# SCH_Minisumo-camara_2026-01-12.net
KiCad netlist of a schematic drawn in EasyEDA
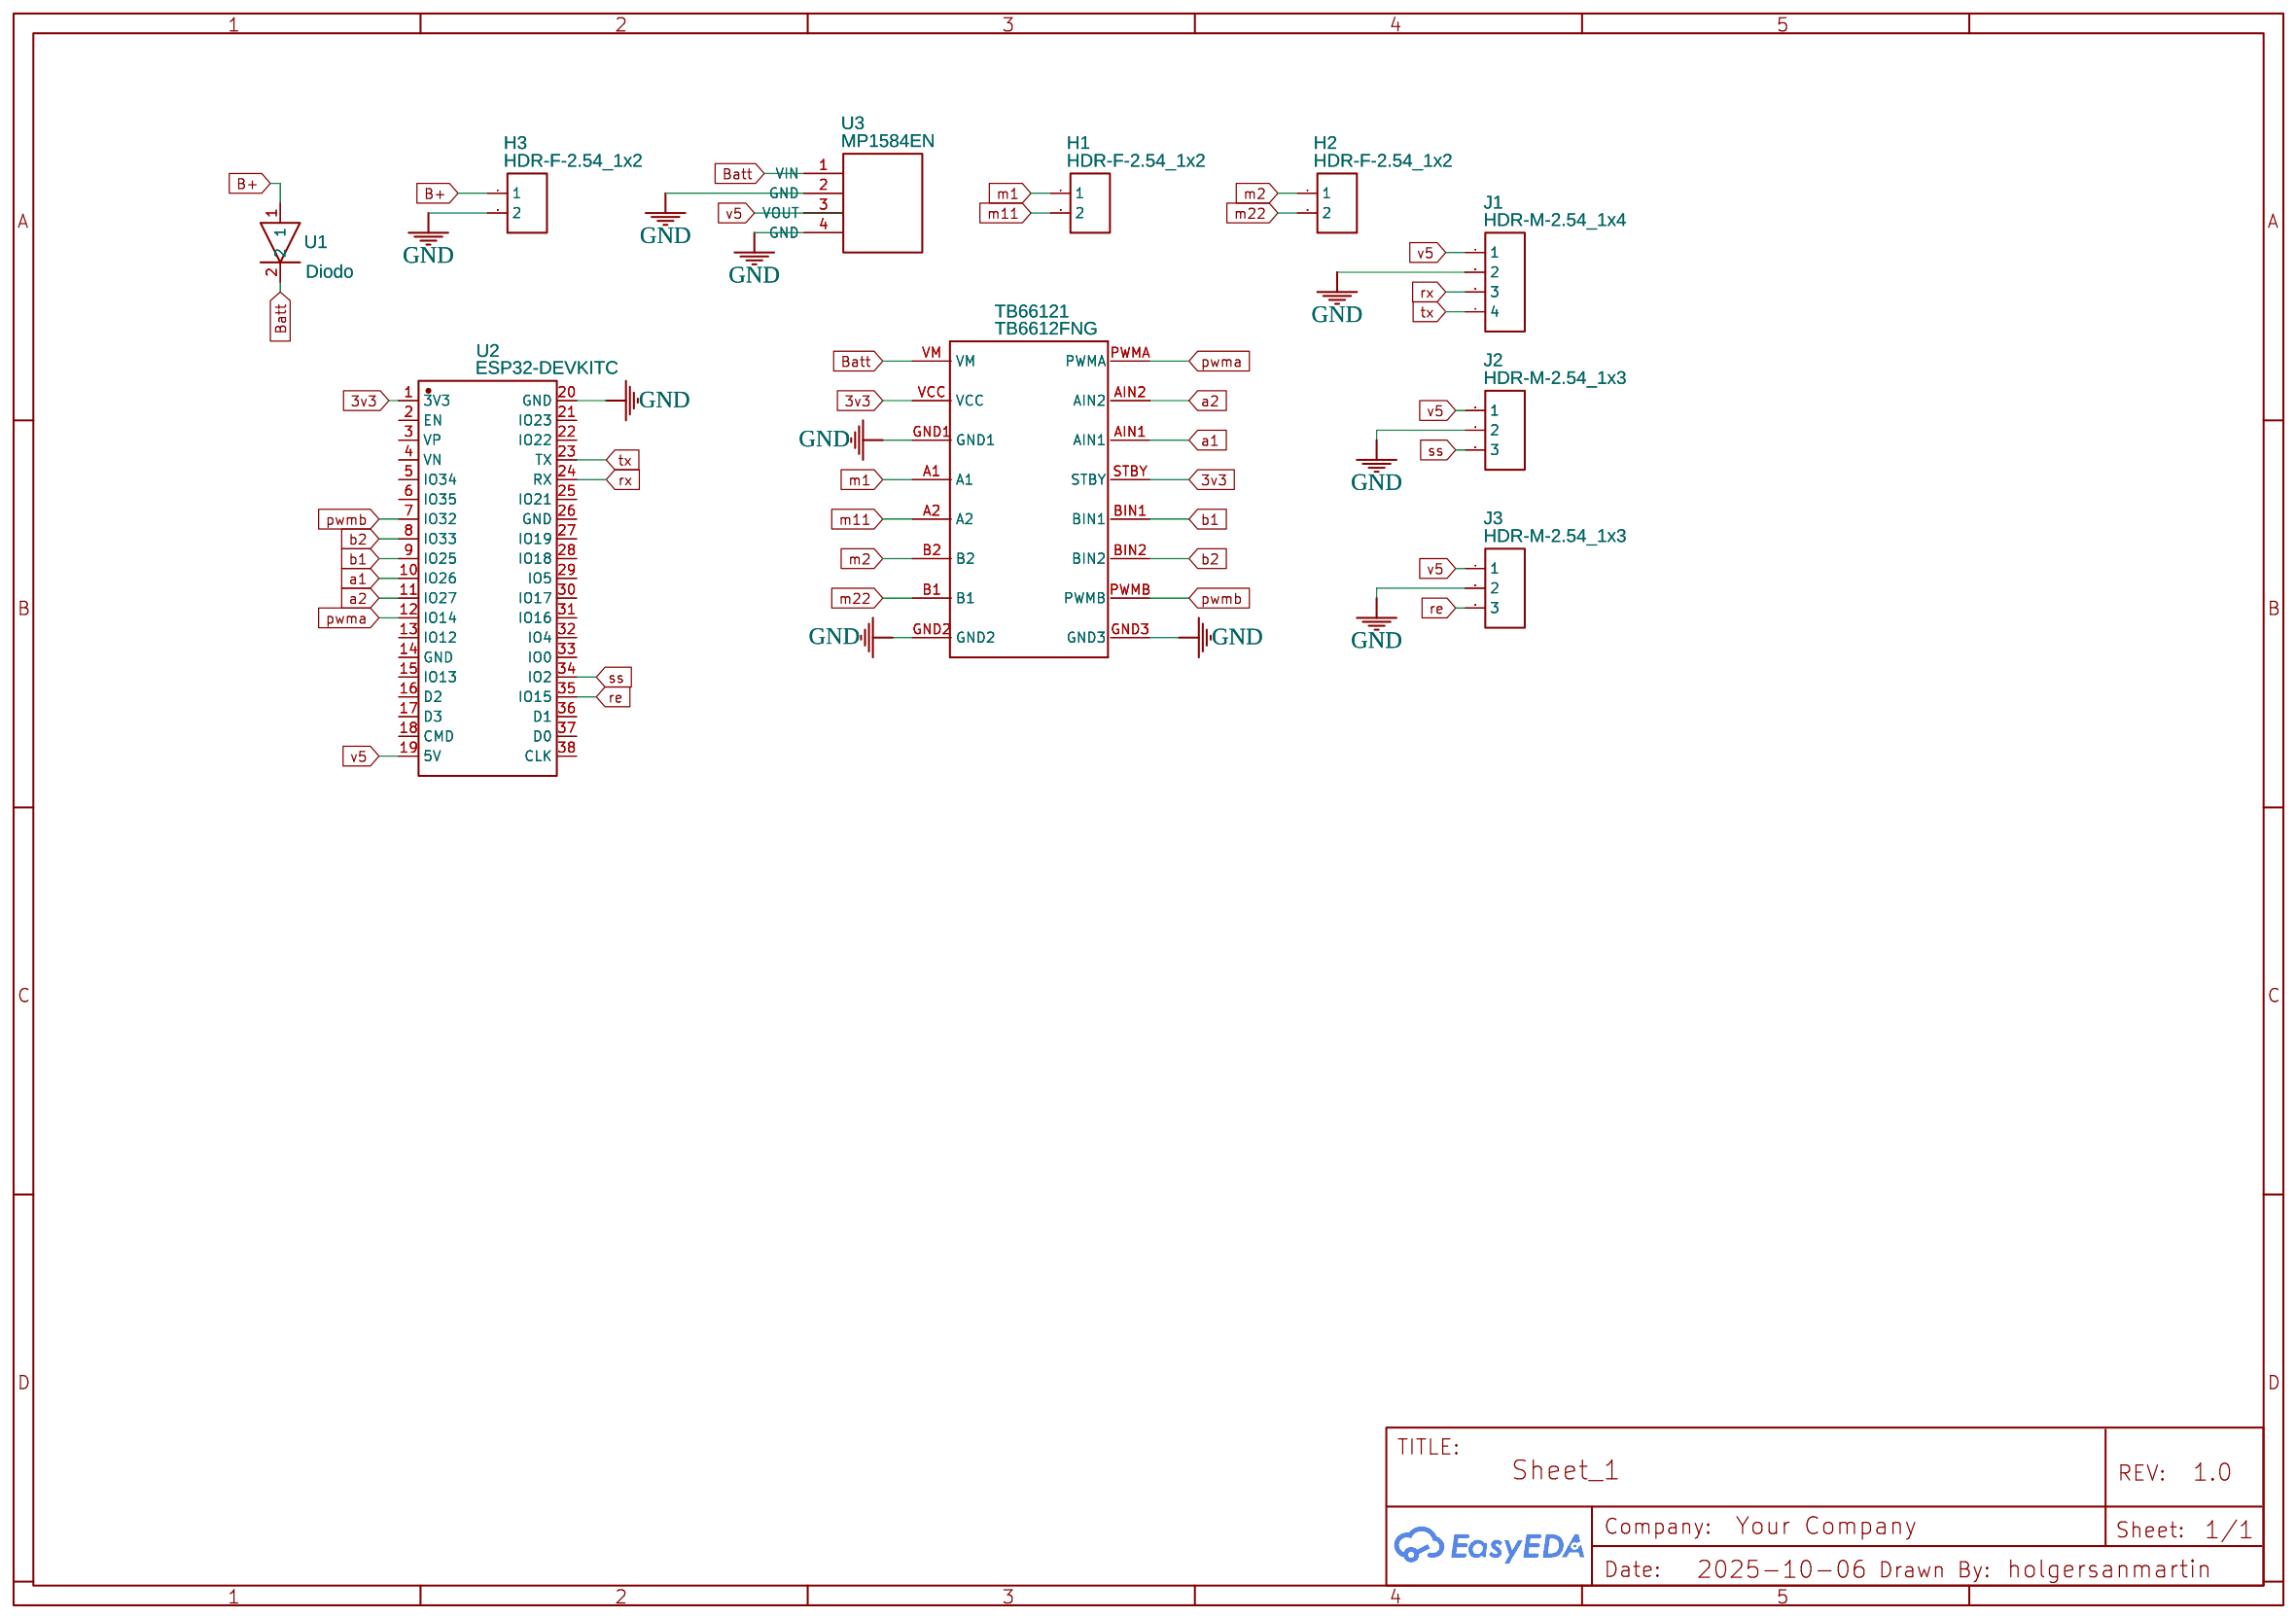
[diagram p0: schematic sheet]

(export (version "E")
  (design (tool "Eeschema 10.0.6"))
  (components
    (comp (ref "H1") (value "HDR-F-2.54_1x2") (libsource (lib "") (part "HDR-F-2.54_1x2")))
    (comp (ref "H2") (value "HDR-F-2.54_1x2") (libsource (lib "") (part "HDR-F-2.54_1x2")))
    (comp (ref "H3") (value "HDR-F-2.54_1x2") (libsource (lib "") (part "HDR-F-2.54_1x2")))
    (comp (ref "J1") (value "HDR-M-2.54_1x4") (libsource (lib "") (part "HDR-M-2.54_1x4")))
    (comp (ref "J2") (value "HDR-M-2.54_1x3") (libsource (lib "") (part "HDR-M-2.54_1x3")))
    (comp (ref "J3") (value "HDR-M-2.54_1x3") (libsource (lib "") (part "HDR-M-2.54_1x3")))
    (comp (ref "TB66121") (value "TB6612FNG") (libsource (lib "") (part "TB6612FNG")))
    (comp (ref "U1") (value "Diodo") (libsource (lib "") (part "Diodo")))
    (comp (ref "U2")
      (value "ESP32-DEVKITC")
      (fields
        (field (name "Manufacturer Part") "ESP32-DevKitC")
        (field (name "Manufacturer") "ESPRESSIF(乐鑫)")
      )
      (libsource (lib "") (part "ESP32-DEVKITC"))
    )
    (comp (ref "U3") (value "MP1584EN") (libsource (lib "") (part "MP1584EN")))
  )
  (nets
    (net (code "1") (name "3v3") (class "Default")
      (node (ref "TB66121") (pin "STBY") (pinfunction "STBY_STBY") (pintype "bidirectional"))
      (node (ref "TB66121") (pin "VCC") (pinfunction "VCC_VCC") (pintype "bidirectional"))
      (node (ref "U2") (pin "1") (pinfunction "3V3_1") (pintype "unspecified"))
    )
    (net (code "2") (name "B+") (class "Default")
      (node (ref "H3") (pin "1") (pinfunction "1_1") (pintype "input"))
      (node (ref "U1") (pin "1") (pinfunction "1_1") (pintype "unspecified"))
    )
    (net (code "3") (name "Batt") (class "Default")
      (node (ref "TB66121") (pin "VM") (pinfunction "VM_VM") (pintype "bidirectional"))
      (node (ref "U1") (pin "2") (pinfunction "2_2") (pintype "unspecified"))
      (node (ref "U3") (pin "1") (pinfunction "VIN_1") (pintype "unspecified"))
    )
    (net (code "4") (name "GND") (class "Default")
      (node (ref "H3") (pin "2") (pinfunction "2_2") (pintype "input"))
      (node (ref "J1") (pin "2") (pinfunction "2_2") (pintype "unspecified"))
      (node (ref "J2") (pin "2") (pinfunction "2_2") (pintype "input"))
      (node (ref "J3") (pin "2") (pinfunction "2_2") (pintype "input"))
      (node (ref "TB66121") (pin "GND1") (pinfunction "GND1_GND1") (pintype "bidirectional"))
      (node (ref "TB66121") (pin "GND2") (pinfunction "GND2_GND2") (pintype "bidirectional"))
      (node (ref "TB66121") (pin "GND3") (pinfunction "GND3_GND3") (pintype "bidirectional"))
      (node (ref "U2") (pin "20") (pinfunction "GND_20") (pintype "unspecified"))
      (node (ref "U3") (pin "2") (pinfunction "GND_2") (pintype "unspecified"))
      (node (ref "U3") (pin "4") (pinfunction "GND_4") (pintype "unspecified"))
    )
    (net (code "5") (name "a1") (class "Default")
      (node (ref "TB66121") (pin "AIN1") (pinfunction "AIN1_AIN1") (pintype "bidirectional"))
      (node (ref "U2") (pin "10") (pinfunction "IO26_10") (pintype "unspecified"))
    )
    (net (code "6") (name "a2") (class "Default")
      (node (ref "TB66121") (pin "AIN2") (pinfunction "AIN2_AIN2") (pintype "bidirectional"))
      (node (ref "U2") (pin "11") (pinfunction "IO27_11") (pintype "unspecified"))
    )
    (net (code "7") (name "b1") (class "Default")
      (node (ref "TB66121") (pin "BIN1") (pinfunction "BIN1_BIN1") (pintype "bidirectional"))
      (node (ref "U2") (pin "9") (pinfunction "IO25_9") (pintype "unspecified"))
    )
    (net (code "8") (name "b2") (class "Default")
      (node (ref "TB66121") (pin "BIN2") (pinfunction "BIN2_BIN2") (pintype "bidirectional"))
      (node (ref "U2") (pin "8") (pinfunction "IO33_8") (pintype "unspecified"))
    )
    (net (code "9") (name "m1") (class "Default")
      (node (ref "H1") (pin "1") (pinfunction "1_1") (pintype "input"))
      (node (ref "TB66121") (pin "A1") (pinfunction "A1_A1") (pintype "bidirectional"))
    )
    (net (code "10") (name "m2") (class "Default")
      (node (ref "H2") (pin "1") (pinfunction "1_1") (pintype "input"))
      (node (ref "TB66121") (pin "B2") (pinfunction "B2_B2") (pintype "bidirectional"))
    )
    (net (code "11") (name "m11") (class "Default")
      (node (ref "H1") (pin "2") (pinfunction "2_2") (pintype "input"))
      (node (ref "TB66121") (pin "A2") (pinfunction "A2_A2") (pintype "bidirectional"))
    )
    (net (code "12") (name "m22") (class "Default")
      (node (ref "H2") (pin "2") (pinfunction "2_2") (pintype "input"))
      (node (ref "TB66121") (pin "B1") (pinfunction "B1_B1") (pintype "bidirectional"))
    )
    (net (code "13") (name "pwma") (class "Default")
      (node (ref "TB66121") (pin "PWMA") (pinfunction "PWMA_PWMA") (pintype "bidirectional"))
      (node (ref "U2") (pin "12") (pinfunction "IO14_12") (pintype "unspecified"))
    )
    (net (code "14") (name "pwmb") (class "Default")
      (node (ref "TB66121") (pin "PWMB") (pinfunction "PWMB_PWMB") (pintype "bidirectional"))
      (node (ref "U2") (pin "7") (pinfunction "IO32_7") (pintype "unspecified"))
    )
    (net (code "15") (name "re") (class "Default")
      (node (ref "J3") (pin "3") (pinfunction "3_3") (pintype "input"))
      (node (ref "U2") (pin "35") (pinfunction "IO15_35") (pintype "unspecified"))
    )
    (net (code "16") (name "rx") (class "Default")
      (node (ref "J1") (pin "3") (pinfunction "3_3") (pintype "unspecified"))
      (node (ref "U2") (pin "24") (pinfunction "RX_24") (pintype "unspecified"))
    )
    (net (code "17") (name "ss") (class "Default")
      (node (ref "J2") (pin "3") (pinfunction "3_3") (pintype "input"))
      (node (ref "U2") (pin "34") (pinfunction "IO2_34") (pintype "unspecified"))
    )
    (net (code "18") (name "tx") (class "Default")
      (node (ref "J1") (pin "4") (pinfunction "4_4") (pintype "unspecified"))
      (node (ref "U2") (pin "23") (pinfunction "TX_23") (pintype "unspecified"))
    )
    (net (code "19") (name "unconnected-(U2-CLK-Pad38)") (class "Default")
      (node (ref "U2") (pin "38") (pinfunction "CLK_38") (pintype "unspecified"))
    )
    (net (code "20") (name "unconnected-(U2-CMD-Pad18)") (class "Default")
      (node (ref "U2") (pin "18") (pinfunction "CMD_18") (pintype "unspecified"))
    )
    (net (code "21") (name "unconnected-(U2-D0-Pad37)") (class "Default")
      (node (ref "U2") (pin "37") (pinfunction "D0_37") (pintype "unspecified"))
    )
    (net (code "22") (name "unconnected-(U2-D1-Pad36)") (class "Default")
      (node (ref "U2") (pin "36") (pinfunction "D1_36") (pintype "unspecified"))
    )
    (net (code "23") (name "unconnected-(U2-D2-Pad16)") (class "Default")
      (node (ref "U2") (pin "16") (pinfunction "D2_16") (pintype "unspecified"))
    )
    (net (code "24") (name "unconnected-(U2-D3-Pad17)") (class "Default")
      (node (ref "U2") (pin "17") (pinfunction "D3_17") (pintype "unspecified"))
    )
    (net (code "25") (name "unconnected-(U2-EN-Pad2)") (class "Default")
      (node (ref "U2") (pin "2") (pinfunction "EN_2") (pintype "unspecified"))
    )
    (net (code "26") (name "unconnected-(U2-GND-Pad14)") (class "Default")
      (node (ref "U2") (pin "14") (pinfunction "GND_14") (pintype "unspecified"))
    )
    (net (code "27") (name "unconnected-(U2-GND-Pad26)") (class "Default")
      (node (ref "U2") (pin "26") (pinfunction "GND_26") (pintype "unspecified"))
    )
    (net (code "28") (name "unconnected-(U2-IO0-Pad33)") (class "Default")
      (node (ref "U2") (pin "33") (pinfunction "IO0_33") (pintype "unspecified"))
    )
    (net (code "29") (name "unconnected-(U2-IO4-Pad32)") (class "Default")
      (node (ref "U2") (pin "32") (pinfunction "IO4_32") (pintype "unspecified"))
    )
    (net (code "30") (name "unconnected-(U2-IO5-Pad29)") (class "Default")
      (node (ref "U2") (pin "29") (pinfunction "IO5_29") (pintype "unspecified"))
    )
    (net (code "31") (name "unconnected-(U2-IO12-Pad13)") (class "Default")
      (node (ref "U2") (pin "13") (pinfunction "IO12_13") (pintype "unspecified"))
    )
    (net (code "32") (name "unconnected-(U2-IO13-Pad15)") (class "Default")
      (node (ref "U2") (pin "15") (pinfunction "IO13_15") (pintype "unspecified"))
    )
    (net (code "33") (name "unconnected-(U2-IO16-Pad31)") (class "Default")
      (node (ref "U2") (pin "31") (pinfunction "IO16_31") (pintype "unspecified"))
    )
    (net (code "34") (name "unconnected-(U2-IO17-Pad30)") (class "Default")
      (node (ref "U2") (pin "30") (pinfunction "IO17_30") (pintype "unspecified"))
    )
    (net (code "35") (name "unconnected-(U2-IO18-Pad28)") (class "Default")
      (node (ref "U2") (pin "28") (pinfunction "IO18_28") (pintype "unspecified"))
    )
    (net (code "36") (name "unconnected-(U2-IO19-Pad27)") (class "Default")
      (node (ref "U2") (pin "27") (pinfunction "IO19_27") (pintype "unspecified"))
    )
    (net (code "37") (name "unconnected-(U2-IO21-Pad25)") (class "Default")
      (node (ref "U2") (pin "25") (pinfunction "IO21_25") (pintype "unspecified"))
    )
    (net (code "38") (name "unconnected-(U2-IO22-Pad22)") (class "Default")
      (node (ref "U2") (pin "22") (pinfunction "IO22_22") (pintype "unspecified"))
    )
    (net (code "39") (name "unconnected-(U2-IO23-Pad21)") (class "Default")
      (node (ref "U2") (pin "21") (pinfunction "IO23_21") (pintype "unspecified"))
    )
    (net (code "40") (name "unconnected-(U2-IO34-Pad5)") (class "Default")
      (node (ref "U2") (pin "5") (pinfunction "IO34_5") (pintype "unspecified"))
    )
    (net (code "41") (name "unconnected-(U2-IO35-Pad6)") (class "Default")
      (node (ref "U2") (pin "6") (pinfunction "IO35_6") (pintype "unspecified"))
    )
    (net (code "42") (name "unconnected-(U2-VN-Pad4)") (class "Default")
      (node (ref "U2") (pin "4") (pinfunction "VN_4") (pintype "unspecified"))
    )
    (net (code "43") (name "unconnected-(U2-VP-Pad3)") (class "Default")
      (node (ref "U2") (pin "3") (pinfunction "VP_3") (pintype "unspecified"))
    )
    (net (code "44") (name "v5") (class "Default")
      (node (ref "J1") (pin "1") (pinfunction "1_1") (pintype "unspecified"))
      (node (ref "J2") (pin "1") (pinfunction "1_1") (pintype "input"))
      (node (ref "J3") (pin "1") (pinfunction "1_1") (pintype "input"))
      (node (ref "U2") (pin "19") (pinfunction "5V_19") (pintype "unspecified"))
      (node (ref "U3") (pin "3") (pinfunction "VOUT_3") (pintype "unspecified"))
    )
  )
)
